# VT.net
KiCad netlist of a schematic drawn in Altium Designer
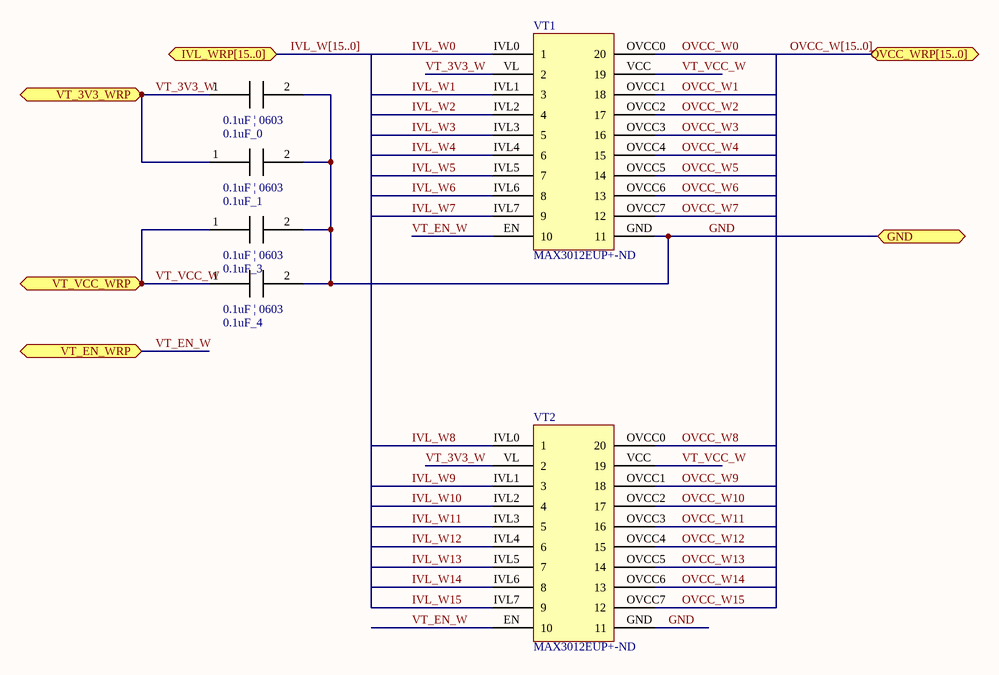
[diagram p0: VT.SchDoc]

(export (version "E")
  (design (tool "Eeschema 10.0.6"))
  (components
    (comp (ref "0.1uF_0")
      (value "0.1uF_0603")
      (footprint "0.1uF_0603")
      (libsource (lib "DUTBoard") (part "0.1uF_0603"))
    )
    (comp (ref "0.1uF_1")
      (value "0.1uF_0603")
      (footprint "0.1uF_0603")
      (libsource (lib "DUTBoard") (part "0.1uF_0603"))
    )
    (comp (ref "0.1uF_3")
      (value "0.1uF_0603")
      (footprint "0.1uF_0603")
      (libsource (lib "DUTBoard") (part "0.1uF_0603"))
    )
    (comp (ref "0.1uF_4")
      (value "0.1uF_0603")
      (footprint "0.1uF_0603")
      (libsource (lib "DUTBoard") (part "0.1uF_0603"))
    )
    (comp (ref "VT1")
      (value "MAX3012EUP+")
      (footprint "VT_TSSOP20")
      (description "IC TRANSLATOR LEVEL 8CH 20-TSSOP")
      (fields
        (field (name "MANUFACTURER") "Maxim Integrated")
        (field (name "SUPPLIER PART NUMBER 1") "MAX3012EUP+-ND")
      )
      (libsource (lib "DUTBoard") (part "MAX3012EUP+"))
    )
    (comp (ref "VT2")
      (value "MAX3012EUP+")
      (footprint "VT_TSSOP20")
      (description "IC TRANSLATOR LEVEL 8CH 20-TSSOP")
      (fields
        (field (name "MANUFACTURER") "Maxim Integrated")
        (field (name "SUPPLIER PART NUMBER 1") "MAX3012EUP+-ND")
      )
      (libsource (lib "DUTBoard") (part "MAX3012EUP+"))
    )
  )
  (nets
    (net (code "1") (name "/GND") (class "Default")
      (node (ref "VT1") (pin "GND") (pinfunction "11_GND") (pintype "passive"))
      (node (ref "VT2") (pin "GND") (pinfunction "11_GND") (pintype "passive"))
    )
    (net (code "2") (name "/IVL_W0") (class "Default")
      (node (ref "VT1") (pin "IVL0") (pinfunction "1_IVL0") (pintype "passive"))
    )
    (net (code "3") (name "/IVL_W1") (class "Default")
      (node (ref "VT1") (pin "IVL1") (pinfunction "3_IVL1") (pintype "passive"))
    )
    (net (code "4") (name "/IVL_W2") (class "Default")
      (node (ref "VT1") (pin "IVL2") (pinfunction "4_IVL2") (pintype "passive"))
    )
    (net (code "5") (name "/IVL_W3") (class "Default")
      (node (ref "VT1") (pin "IVL3") (pinfunction "5_IVL3") (pintype "passive"))
    )
    (net (code "6") (name "/IVL_W4") (class "Default")
      (node (ref "VT1") (pin "IVL4") (pinfunction "6_IVL4") (pintype "passive"))
    )
    (net (code "7") (name "/IVL_W5") (class "Default")
      (node (ref "VT1") (pin "IVL5") (pinfunction "7_IVL5") (pintype "passive"))
    )
    (net (code "8") (name "/IVL_W6") (class "Default")
      (node (ref "VT1") (pin "IVL6") (pinfunction "8_IVL6") (pintype "passive"))
    )
    (net (code "9") (name "/IVL_W7") (class "Default")
      (node (ref "VT1") (pin "IVL7") (pinfunction "9_IVL7") (pintype "passive"))
    )
    (net (code "10") (name "/IVL_W8") (class "Default")
      (node (ref "VT2") (pin "IVL0") (pinfunction "1_IVL0") (pintype "passive"))
    )
    (net (code "11") (name "/IVL_W9") (class "Default")
      (node (ref "VT2") (pin "IVL1") (pinfunction "3_IVL1") (pintype "passive"))
    )
    (net (code "12") (name "/IVL_W10") (class "Default")
      (node (ref "VT2") (pin "IVL2") (pinfunction "4_IVL2") (pintype "passive"))
    )
    (net (code "13") (name "/IVL_W11") (class "Default")
      (node (ref "VT2") (pin "IVL3") (pinfunction "5_IVL3") (pintype "passive"))
    )
    (net (code "14") (name "/IVL_W12") (class "Default")
      (node (ref "VT2") (pin "IVL4") (pinfunction "6_IVL4") (pintype "passive"))
    )
    (net (code "15") (name "/IVL_W13") (class "Default")
      (node (ref "VT2") (pin "IVL5") (pinfunction "7_IVL5") (pintype "passive"))
    )
    (net (code "16") (name "/IVL_W14") (class "Default")
      (node (ref "VT2") (pin "IVL6") (pinfunction "8_IVL6") (pintype "passive"))
    )
    (net (code "17") (name "/IVL_W15") (class "Default")
      (node (ref "VT2") (pin "IVL7") (pinfunction "9_IVL7") (pintype "passive"))
    )
    (net (code "19") (name "/OVCC_W0") (class "Default")
      (node (ref "VT1") (pin "OVCC0") (pinfunction "20_OVCC0") (pintype "passive"))
    )
    (net (code "20") (name "/OVCC_W1") (class "Default")
      (node (ref "VT1") (pin "OVCC1") (pinfunction "18_OVCC1") (pintype "passive"))
    )
    (net (code "21") (name "/OVCC_W2") (class "Default")
      (node (ref "VT1") (pin "OVCC2") (pinfunction "17_OVCC2") (pintype "passive"))
    )
    (net (code "22") (name "/OVCC_W3") (class "Default")
      (node (ref "VT1") (pin "OVCC3") (pinfunction "16_OVCC3") (pintype "passive"))
    )
    (net (code "23") (name "/OVCC_W4") (class "Default")
      (node (ref "VT1") (pin "OVCC4") (pinfunction "15_OVCC4") (pintype "passive"))
    )
    (net (code "24") (name "/OVCC_W5") (class "Default")
      (node (ref "VT1") (pin "OVCC5") (pinfunction "14_OVCC5") (pintype "passive"))
    )
    (net (code "25") (name "/OVCC_W6") (class "Default")
      (node (ref "VT1") (pin "OVCC6") (pinfunction "13_OVCC6") (pintype "passive"))
    )
    (net (code "26") (name "/OVCC_W7") (class "Default")
      (node (ref "VT1") (pin "OVCC7") (pinfunction "12_OVCC7") (pintype "passive"))
    )
    (net (code "27") (name "/OVCC_W8") (class "Default")
      (node (ref "VT2") (pin "OVCC0") (pinfunction "20_OVCC0") (pintype "passive"))
    )
    (net (code "28") (name "/OVCC_W9") (class "Default")
      (node (ref "VT2") (pin "OVCC1") (pinfunction "18_OVCC1") (pintype "passive"))
    )
    (net (code "29") (name "/OVCC_W10") (class "Default")
      (node (ref "VT2") (pin "OVCC2") (pinfunction "17_OVCC2") (pintype "passive"))
    )
    (net (code "30") (name "/OVCC_W11") (class "Default")
      (node (ref "VT2") (pin "OVCC3") (pinfunction "16_OVCC3") (pintype "passive"))
    )
    (net (code "31") (name "/OVCC_W12") (class "Default")
      (node (ref "VT2") (pin "OVCC4") (pinfunction "15_OVCC4") (pintype "passive"))
    )
    (net (code "32") (name "/OVCC_W13") (class "Default")
      (node (ref "VT2") (pin "OVCC5") (pinfunction "14_OVCC5") (pintype "passive"))
    )
    (net (code "33") (name "/OVCC_W14") (class "Default")
      (node (ref "VT2") (pin "OVCC6") (pinfunction "13_OVCC6") (pintype "passive"))
    )
    (net (code "34") (name "/OVCC_W15") (class "Default")
      (node (ref "VT2") (pin "OVCC7") (pinfunction "12_OVCC7") (pintype "passive"))
    )
    (net (code "36") (name "/VT_3V3_W") (class "Default")
      (node (ref "0.1uF_0") (pin "1") (pinfunction "1_1") (pintype "passive"))
      (node (ref "0.1uF_1") (pin "1") (pinfunction "1_1") (pintype "passive"))
      (node (ref "VT1") (pin "VL") (pinfunction "2_VL") (pintype "passive"))
      (node (ref "VT2") (pin "VL") (pinfunction "2_VL") (pintype "passive"))
    )
    (net (code "37") (name "/VT_EN_W") (class "Default")
      (node (ref "VT1") (pin "EN") (pinfunction "10_EN") (pintype "passive"))
      (node (ref "VT2") (pin "EN") (pinfunction "10_EN") (pintype "passive"))
    )
    (net (code "38") (name "/VT_VCC_W") (class "Default")
      (node (ref "0.1uF_3") (pin "1") (pinfunction "1_1") (pintype "passive"))
      (node (ref "0.1uF_4") (pin "1") (pinfunction "1_1") (pintype "passive"))
      (node (ref "VT1") (pin "VCC") (pinfunction "19_VCC") (pintype "passive"))
      (node (ref "VT2") (pin "VCC") (pinfunction "19_VCC") (pintype "passive"))
    )
    (net (code "39") (name "unconnected-(0.1uF_0-Pad2)") (class "Default")
      (node (ref "0.1uF_0") (pin "2") (pinfunction "2_2") (pintype "passive"))
    )
    (net (code "40") (name "unconnected-(0.1uF_1-Pad2)") (class "Default")
      (node (ref "0.1uF_1") (pin "2") (pinfunction "2_2") (pintype "passive"))
    )
    (net (code "41") (name "unconnected-(0.1uF_3-Pad2)") (class "Default")
      (node (ref "0.1uF_3") (pin "2") (pinfunction "2_2") (pintype "passive"))
    )
    (net (code "42") (name "unconnected-(0.1uF_4-Pad2)") (class "Default")
      (node (ref "0.1uF_4") (pin "2") (pinfunction "2_2") (pintype "passive"))
    )
  )
)
